# SCH_POC-QTR-8A_2022-11-29.net
KiCad netlist of a schematic drawn in EasyEDA
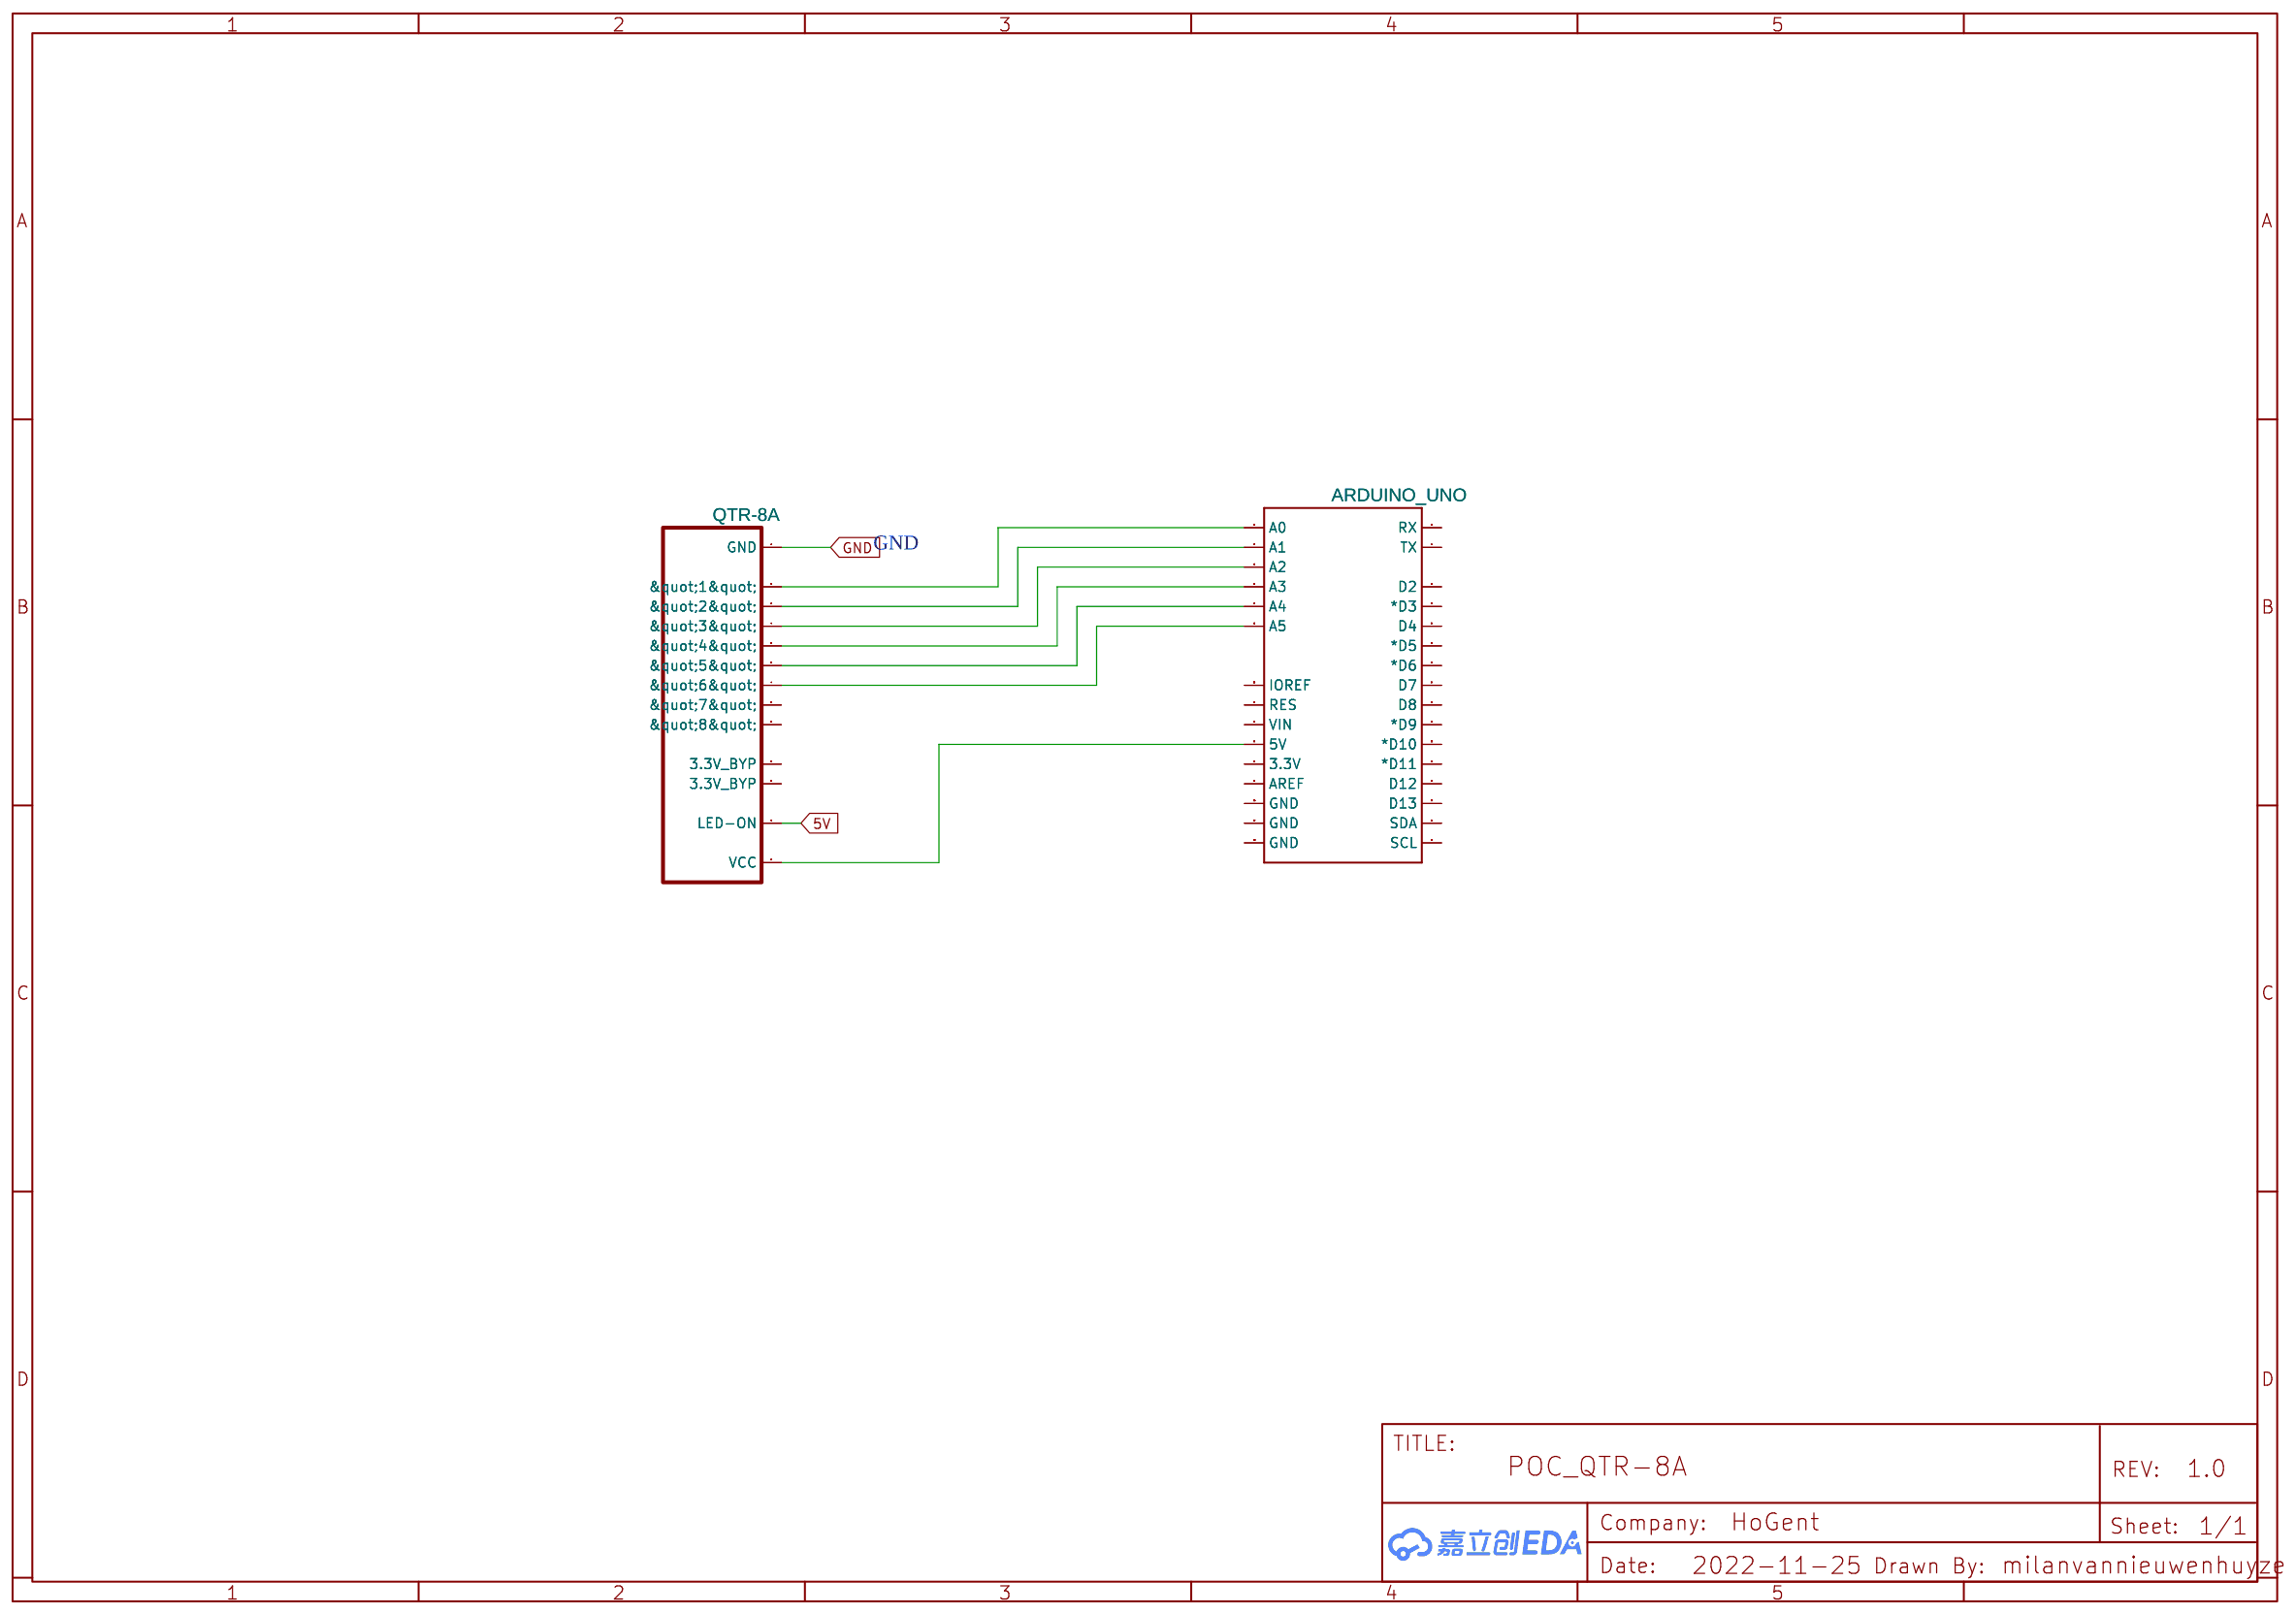
[diagram p0: schematic sheet]

(export (version "E")
  (design (tool "Eeschema 10.0.6"))
  (components
    (comp (ref "U1") (value "ARDUINO_UNO") (libsource (lib "") (part "ARDUINO_R3_SHIELD")))
    (comp (ref "U2")
      (value "QTR-8A")
      (fields (field (name "BOM_Supplier Part") "960"))
      (libsource (lib "") (part "QTR-8A"))
    )
  )
  (nets
    (net (code "1") (name "5V") (class "Default")
      (node (ref "U2") (pin "12") (pinfunction "LED-ON_12") (pintype "unspecified"))
    )
    (net (code "2") (name "GND") (class "Default")
      (node (ref "U2") (pin "1") (pinfunction "GND_1") (pintype "unspecified"))
    )
    (net (code "3") (name "Net-(U2-&quot;1&quot;)") (class "Default")
      (node (ref "U1") (pin "A0") (pinfunction "A0_A0") (pintype "unspecified"))
      (node (ref "U2") (pin "2") (pinfunction "&quot;1&quot;_2") (pintype "unspecified"))
    )
    (net (code "4") (name "Net-(U2-&quot;2&quot;)") (class "Default")
      (node (ref "U1") (pin "A1") (pinfunction "A1_A1") (pintype "unspecified"))
      (node (ref "U2") (pin "3") (pinfunction "&quot;2&quot;_3") (pintype "unspecified"))
    )
    (net (code "5") (name "Net-(U2-&quot;3&quot;)") (class "Default")
      (node (ref "U1") (pin "A2") (pinfunction "A2_A2") (pintype "unspecified"))
      (node (ref "U2") (pin "4") (pinfunction "&quot;3&quot;_4") (pintype "unspecified"))
    )
    (net (code "6") (name "Net-(U2-&quot;4&quot;)") (class "Default")
      (node (ref "U1") (pin "A3") (pinfunction "A3_A3") (pintype "unspecified"))
      (node (ref "U2") (pin "5") (pinfunction "&quot;4&quot;_5") (pintype "unspecified"))
    )
    (net (code "7") (name "Net-(U2-&quot;5&quot;)") (class "Default")
      (node (ref "U1") (pin "A4") (pinfunction "A4_A4") (pintype "unspecified"))
      (node (ref "U2") (pin "6") (pinfunction "&quot;5&quot;_6") (pintype "unspecified"))
    )
    (net (code "8") (name "Net-(U2-&quot;6&quot;)") (class "Default")
      (node (ref "U1") (pin "A5") (pinfunction "A5_A5") (pintype "unspecified"))
      (node (ref "U2") (pin "7") (pinfunction "&quot;6&quot;_7") (pintype "unspecified"))
    )
    (net (code "9") (name "Net-(U2-VCC)") (class "Default")
      (node (ref "U1") (pin "5V") (pinfunction "5V_5V") (pintype "unspecified"))
      (node (ref "U2") (pin "12") (pinfunction "VCC_12") (pintype "unspecified"))
    )
    (net (code "10") (name "unconnected-(U1-*D3-PadD3)") (class "Default")
      (node (ref "U1") (pin "D3") (pinfunction "*D3_D3") (pintype "unspecified"))
    )
    (net (code "11") (name "unconnected-(U1-*D5-PadD5)") (class "Default")
      (node (ref "U1") (pin "D5") (pinfunction "*D5_D5") (pintype "unspecified"))
    )
    (net (code "12") (name "unconnected-(U1-*D6-PadD6)") (class "Default")
      (node (ref "U1") (pin "D6") (pinfunction "*D6_D6") (pintype "unspecified"))
    )
    (net (code "13") (name "unconnected-(U1-*D9-PadD9)") (class "Default")
      (node (ref "U1") (pin "D9") (pinfunction "*D9_D9") (pintype "unspecified"))
    )
    (net (code "14") (name "unconnected-(U1-*D10-PadD10)") (class "Default")
      (node (ref "U1") (pin "D10") (pinfunction "*D10_D10") (pintype "unspecified"))
    )
    (net (code "15") (name "unconnected-(U1-*D11-PadD11)") (class "Default")
      (node (ref "U1") (pin "D11") (pinfunction "*D11_D11") (pintype "unspecified"))
    )
    (net (code "16") (name "unconnected-(U1-GND-PadGND@0)") (class "Default")
      (node (ref "U1") (pin "GND@0") (pinfunction "GND_GND@0") (pintype "unspecified"))
    )
    (net (code "17") (name "unconnected-(U1-GND-PadGND@1)") (class "Default")
      (node (ref "U1") (pin "GND@1") (pinfunction "GND_GND@1") (pintype "unspecified"))
    )
    (net (code "18") (name "unconnected-(U1-GND-PadGND@2)") (class "Default")
      (node (ref "U1") (pin "GND@2") (pinfunction "GND_GND@2") (pintype "unspecified"))
    )
    (net (code "19") (name "unconnected-(U1-Pad3.3V)") (class "Default")
      (node (ref "U1") (pin "3.3V") (pinfunction "3.3V_3.3V") (pintype "unspecified"))
    )
    (net (code "20") (name "unconnected-(U1-PadAREF)") (class "Default")
      (node (ref "U1") (pin "AREF") (pinfunction "AREF_AREF") (pintype "unspecified"))
    )
    (net (code "21") (name "unconnected-(U1-PadD2)") (class "Default")
      (node (ref "U1") (pin "D2") (pinfunction "D2_D2") (pintype "unspecified"))
    )
    (net (code "22") (name "unconnected-(U1-PadD4)") (class "Default")
      (node (ref "U1") (pin "D4") (pinfunction "D4_D4") (pintype "unspecified"))
    )
    (net (code "23") (name "unconnected-(U1-PadD7)") (class "Default")
      (node (ref "U1") (pin "D7") (pinfunction "D7_D7") (pintype "unspecified"))
    )
    (net (code "24") (name "unconnected-(U1-PadD8)") (class "Default")
      (node (ref "U1") (pin "D8") (pinfunction "D8_D8") (pintype "unspecified"))
    )
    (net (code "25") (name "unconnected-(U1-PadD12)") (class "Default")
      (node (ref "U1") (pin "D12") (pinfunction "D12_D12") (pintype "unspecified"))
    )
    (net (code "26") (name "unconnected-(U1-PadD13)") (class "Default")
      (node (ref "U1") (pin "D13") (pinfunction "D13_D13") (pintype "unspecified"))
    )
    (net (code "27") (name "unconnected-(U1-PadIOREF)") (class "Default")
      (node (ref "U1") (pin "IOREF") (pinfunction "IOREF_IOREF") (pintype "unspecified"))
    )
    (net (code "28") (name "unconnected-(U1-PadRES)") (class "Default")
      (node (ref "U1") (pin "RES") (pinfunction "RES_RES") (pintype "unspecified"))
    )
    (net (code "29") (name "unconnected-(U1-PadRX)") (class "Default")
      (node (ref "U1") (pin "RX") (pinfunction "RX_RX") (pintype "unspecified"))
    )
    (net (code "30") (name "unconnected-(U1-PadSCL)") (class "Default")
      (node (ref "U1") (pin "SCL") (pinfunction "SCL_SCL") (pintype "unspecified"))
    )
    (net (code "31") (name "unconnected-(U1-PadSDA)") (class "Default")
      (node (ref "U1") (pin "SDA") (pinfunction "SDA_SDA") (pintype "unspecified"))
    )
    (net (code "32") (name "unconnected-(U1-PadTX)") (class "Default")
      (node (ref "U1") (pin "TX") (pinfunction "TX_TX") (pintype "unspecified"))
    )
    (net (code "33") (name "unconnected-(U1-PadVIN)") (class "Default")
      (node (ref "U1") (pin "VIN") (pinfunction "VIN_VIN") (pintype "unspecified"))
    )
    (net (code "34") (name "unconnected-(U2-&quot;7&quot;-Pad8)") (class "Default")
      (node (ref "U2") (pin "8") (pinfunction "&quot;7&quot;_8") (pintype "unspecified"))
    )
    (net (code "35") (name "unconnected-(U2-&quot;8&quot;-Pad9)") (class "Default")
      (node (ref "U2") (pin "9") (pinfunction "&quot;8&quot;_9") (pintype "unspecified"))
    )
    (net (code "36") (name "unconnected-(U2-3.3V_BYP-Pad10)") (class "Default")
      (node (ref "U2") (pin "10") (pinfunction "3.3V_BYP_10") (pintype "unspecified"))
    )
    (net (code "37") (name "unconnected-(U2-3.3V_BYP-Pad11)") (class "Default")
      (node (ref "U2") (pin "11") (pinfunction "3.3V_BYP_11") (pintype "unspecified"))
    )
  )
)
